# DataControlBoard-RPi.net
KiCad netlist of a schematic drawn in EAGLE
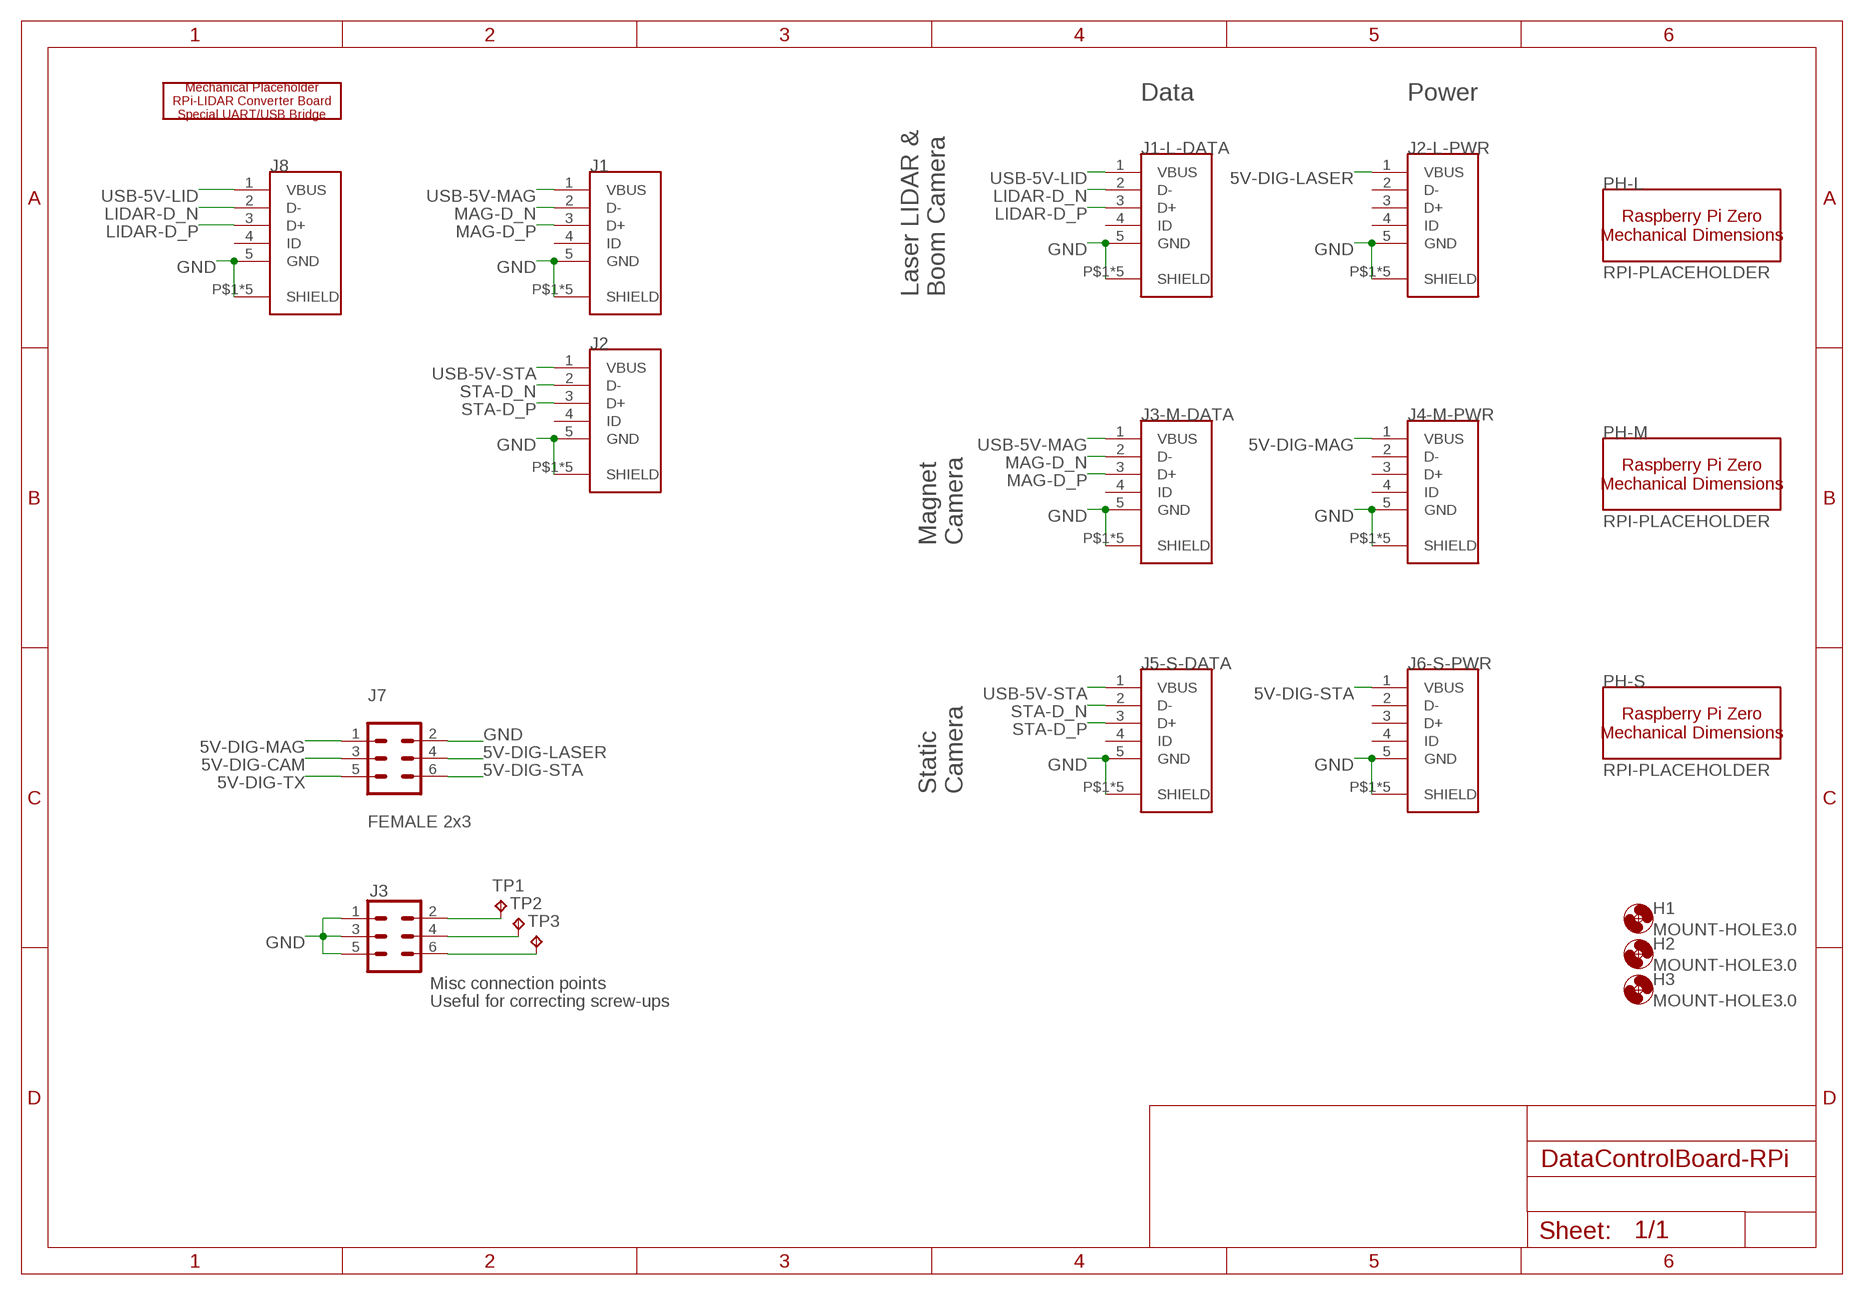
[diagram p0: schematic, sheet 1]

(export (version "E")
  (design (tool "Eeschema 10.0.6"))
  (components
    (comp (ref "H1")
      (value "MOUNT-HOLE3.0")
      (footprint "eagle-import:3,0")
      (libsource (lib "eagle-import") (part "MOUNT-HOLE3.0"))
    )
    (comp (ref "H2")
      (value "MOUNT-HOLE3.0")
      (footprint "eagle-import:3,0")
      (libsource (lib "eagle-import") (part "MOUNT-HOLE3.0"))
    )
    (comp (ref "H3")
      (value "MOUNT-HOLE3.0")
      (footprint "eagle-import:3,0")
      (libsource (lib "eagle-import") (part "MOUNT-HOLE3.0"))
    )
    (comp (ref "J1")
      (value "USB3150-30-130-AMANUFACTURABLE")
      (footprint "eagle-import:GCT_USB3150-30-EASIER")
      (libsource (lib "eagle-import") (part "USB3150-30-130-AMANUFACTURABLE"))
    )
    (comp (ref "J1-L-DATA")
      (value "USB3150-30-130-AMANUFACTURABLE")
      (footprint "eagle-import:GCT_USB3150-30-EASIER")
      (libsource (lib "eagle-import") (part "USB3150-30-130-AMANUFACTURABLE"))
    )
    (comp (ref "J2")
      (value "USB3150-30-130-AMANUFACTURABLE")
      (footprint "eagle-import:GCT_USB3150-30-EASIER")
      (libsource (lib "eagle-import") (part "USB3150-30-130-AMANUFACTURABLE"))
    )
    (comp (ref "J2-L-PWR")
      (value "USB3150-30-130-AMANUFACTURABLE")
      (footprint "eagle-import:GCT_USB3150-30-EASIER")
      (libsource (lib "eagle-import") (part "USB3150-30-130-AMANUFACTURABLE"))
    )
    (comp (ref "J3")
      (value "CONN_03X22X3_SILK_MALE_PTH")
      (footprint "eagle-import:2X3")
      (libsource (lib "eagle-import") (part "CONN_03X22X3_SILK_MALE_PTH"))
    )
    (comp (ref "J3-M-DATA")
      (value "USB3150-30-130-AMANUFACTURABLE")
      (footprint "eagle-import:GCT_USB3150-30-EASIER")
      (libsource (lib "eagle-import") (part "USB3150-30-130-AMANUFACTURABLE"))
    )
    (comp (ref "J4-M-PWR")
      (value "USB3150-30-130-AMANUFACTURABLE")
      (footprint "eagle-import:GCT_USB3150-30-EASIER")
      (libsource (lib "eagle-import") (part "USB3150-30-130-AMANUFACTURABLE"))
    )
    (comp (ref "J5-S-DATA")
      (value "USB3150-30-130-AMANUFACTURABLE")
      (footprint "eagle-import:GCT_USB3150-30-EASIER")
      (libsource (lib "eagle-import") (part "USB3150-30-130-AMANUFACTURABLE"))
    )
    (comp (ref "J6-S-PWR")
      (value "USB3150-30-130-AMANUFACTURABLE")
      (footprint "eagle-import:GCT_USB3150-30-EASIER")
      (libsource (lib "eagle-import") (part "USB3150-30-130-AMANUFACTURABLE"))
    )
    (comp (ref "J7")
      (value "FEMALE 2x3")
      (footprint "eagle-import:2X3")
      (libsource (lib "eagle-import") (part "CONN_03X2FEMALE"))
    )
    (comp (ref "J8")
      (value "USB3150-30-130-AMANUFACTURABLE")
      (footprint "eagle-import:GCT_USB3150-30-EASIER")
      (libsource (lib "eagle-import") (part "USB3150-30-130-AMANUFACTURABLE"))
    )
    (comp (ref "PH-L")
      (value "RPI-PLACEHOLDER")
      (footprint "eagle-import:RPI-ZERO-EDGE")
      (libsource (lib "eagle-import") (part "RPI-PLACEHOLDER"))
    )
    (comp (ref "PH-M")
      (value "RPI-PLACEHOLDER")
      (footprint "eagle-import:RPI-ZERO-EDGE")
      (libsource (lib "eagle-import") (part "RPI-PLACEHOLDER"))
    )
    (comp (ref "PH-S")
      (value "RPI-PLACEHOLDER")
      (footprint "eagle-import:RPI-ZERO-EDGE")
      (libsource (lib "eagle-import") (part "RPI-PLACEHOLDER"))
    )
    (comp (ref "TP1")
      (value "TPPAD1-17")
      (footprint "eagle-import:P1-17")
      (libsource (lib "eagle-import") (part "TPPAD1-17"))
    )
    (comp (ref "TP2")
      (value "TPPAD1-17")
      (footprint "eagle-import:P1-17")
      (libsource (lib "eagle-import") (part "TPPAD1-17"))
    )
    (comp (ref "TP3")
      (value "TPPAD1-17")
      (footprint "eagle-import:P1-17")
      (libsource (lib "eagle-import") (part "TPPAD1-17"))
    )
    (comp (ref "U$4")
      (value "LIDAR-CONV-PLACEHOLDER")
      (footprint "eagle-import:LIDAR-PLACEHOLDER")
      (libsource (lib "eagle-import") (part "LIDAR-CONV-PLACEHOLDER"))
    )
  )
  (nets
    (net (code "1") (name "/5V-DIG-CAM") (class "Default")
      (node (ref "J7") (pin "3") (pinfunction "3_3") (pintype "bidirectional"))
    )
    (net (code "2") (name "/5V-DIG-LASER") (class "Default")
      (node (ref "J2-L-PWR") (pin "1") (pinfunction "VBUS_1") (pintype "passive"))
      (node (ref "J7") (pin "4") (pinfunction "4_4") (pintype "bidirectional"))
    )
    (net (code "3") (name "/5V-DIG-MAG") (class "Default")
      (node (ref "J4-M-PWR") (pin "1") (pinfunction "VBUS_1") (pintype "passive"))
      (node (ref "J7") (pin "1") (pinfunction "1_1") (pintype "bidirectional"))
    )
    (net (code "4") (name "/5V-DIG-STA") (class "Default")
      (node (ref "J6-S-PWR") (pin "1") (pinfunction "VBUS_1") (pintype "passive"))
      (node (ref "J7") (pin "6") (pinfunction "6_6") (pintype "bidirectional"))
    )
    (net (code "5") (name "/5V-DIG-TX") (class "Default")
      (node (ref "J7") (pin "5") (pinfunction "5_5") (pintype "bidirectional"))
    )
    (net (code "6") (name "/GND") (class "Default")
      (node (ref "J1") (pin "5") (pinfunction "GND_5") (pintype "passive"))
      (node (ref "J1") (pin "P$1") (pinfunction "SHIELD_P$1") (pintype "passive"))
      (node (ref "J1") (pin "S3") (pinfunction "SHIELD_S3") (pintype "passive"))
      (node (ref "J1") (pin "S4") (pinfunction "SHIELD_S4") (pintype "passive"))
      (node (ref "J1") (pin "S5") (pinfunction "SHIELD_S5") (pintype "passive"))
      (node (ref "J1") (pin "S6") (pinfunction "SHIELD_S6") (pintype "passive"))
      (node (ref "J1-L-DATA") (pin "5") (pinfunction "GND_5") (pintype "passive"))
      (node (ref "J1-L-DATA") (pin "P$1") (pinfunction "SHIELD_P$1") (pintype "passive"))
      (node (ref "J1-L-DATA") (pin "S3") (pinfunction "SHIELD_S3") (pintype "passive"))
      (node (ref "J1-L-DATA") (pin "S4") (pinfunction "SHIELD_S4") (pintype "passive"))
      (node (ref "J1-L-DATA") (pin "S5") (pinfunction "SHIELD_S5") (pintype "passive"))
      (node (ref "J1-L-DATA") (pin "S6") (pinfunction "SHIELD_S6") (pintype "passive"))
      (node (ref "J2") (pin "5") (pinfunction "GND_5") (pintype "passive"))
      (node (ref "J2") (pin "P$1") (pinfunction "SHIELD_P$1") (pintype "passive"))
      (node (ref "J2") (pin "S3") (pinfunction "SHIELD_S3") (pintype "passive"))
      (node (ref "J2") (pin "S4") (pinfunction "SHIELD_S4") (pintype "passive"))
      (node (ref "J2") (pin "S5") (pinfunction "SHIELD_S5") (pintype "passive"))
      (node (ref "J2") (pin "S6") (pinfunction "SHIELD_S6") (pintype "passive"))
      (node (ref "J2-L-PWR") (pin "5") (pinfunction "GND_5") (pintype "passive"))
      (node (ref "J2-L-PWR") (pin "P$1") (pinfunction "SHIELD_P$1") (pintype "passive"))
      (node (ref "J2-L-PWR") (pin "S3") (pinfunction "SHIELD_S3") (pintype "passive"))
      (node (ref "J2-L-PWR") (pin "S4") (pinfunction "SHIELD_S4") (pintype "passive"))
      (node (ref "J2-L-PWR") (pin "S5") (pinfunction "SHIELD_S5") (pintype "passive"))
      (node (ref "J2-L-PWR") (pin "S6") (pinfunction "SHIELD_S6") (pintype "passive"))
      (node (ref "J3") (pin "1") (pinfunction "1_1") (pintype "bidirectional"))
      (node (ref "J3") (pin "3") (pinfunction "3_3") (pintype "bidirectional"))
      (node (ref "J3") (pin "5") (pinfunction "5_5") (pintype "bidirectional"))
      (node (ref "J3-M-DATA") (pin "5") (pinfunction "GND_5") (pintype "passive"))
      (node (ref "J3-M-DATA") (pin "P$1") (pinfunction "SHIELD_P$1") (pintype "passive"))
      (node (ref "J3-M-DATA") (pin "S3") (pinfunction "SHIELD_S3") (pintype "passive"))
      (node (ref "J3-M-DATA") (pin "S4") (pinfunction "SHIELD_S4") (pintype "passive"))
      (node (ref "J3-M-DATA") (pin "S5") (pinfunction "SHIELD_S5") (pintype "passive"))
      (node (ref "J3-M-DATA") (pin "S6") (pinfunction "SHIELD_S6") (pintype "passive"))
      (node (ref "J4-M-PWR") (pin "5") (pinfunction "GND_5") (pintype "passive"))
      (node (ref "J4-M-PWR") (pin "P$1") (pinfunction "SHIELD_P$1") (pintype "passive"))
      (node (ref "J4-M-PWR") (pin "S3") (pinfunction "SHIELD_S3") (pintype "passive"))
      (node (ref "J4-M-PWR") (pin "S4") (pinfunction "SHIELD_S4") (pintype "passive"))
      (node (ref "J4-M-PWR") (pin "S5") (pinfunction "SHIELD_S5") (pintype "passive"))
      (node (ref "J4-M-PWR") (pin "S6") (pinfunction "SHIELD_S6") (pintype "passive"))
      (node (ref "J5-S-DATA") (pin "5") (pinfunction "GND_5") (pintype "passive"))
      (node (ref "J5-S-DATA") (pin "P$1") (pinfunction "SHIELD_P$1") (pintype "passive"))
      (node (ref "J5-S-DATA") (pin "S3") (pinfunction "SHIELD_S3") (pintype "passive"))
      (node (ref "J5-S-DATA") (pin "S4") (pinfunction "SHIELD_S4") (pintype "passive"))
      (node (ref "J5-S-DATA") (pin "S5") (pinfunction "SHIELD_S5") (pintype "passive"))
      (node (ref "J5-S-DATA") (pin "S6") (pinfunction "SHIELD_S6") (pintype "passive"))
      (node (ref "J6-S-PWR") (pin "5") (pinfunction "GND_5") (pintype "passive"))
      (node (ref "J6-S-PWR") (pin "P$1") (pinfunction "SHIELD_P$1") (pintype "passive"))
      (node (ref "J6-S-PWR") (pin "S3") (pinfunction "SHIELD_S3") (pintype "passive"))
      (node (ref "J6-S-PWR") (pin "S4") (pinfunction "SHIELD_S4") (pintype "passive"))
      (node (ref "J6-S-PWR") (pin "S5") (pinfunction "SHIELD_S5") (pintype "passive"))
      (node (ref "J6-S-PWR") (pin "S6") (pinfunction "SHIELD_S6") (pintype "passive"))
      (node (ref "J7") (pin "2") (pinfunction "2_2") (pintype "bidirectional"))
      (node (ref "J8") (pin "5") (pinfunction "GND_5") (pintype "passive"))
      (node (ref "J8") (pin "P$1") (pinfunction "SHIELD_P$1") (pintype "passive"))
      (node (ref "J8") (pin "S3") (pinfunction "SHIELD_S3") (pintype "passive"))
      (node (ref "J8") (pin "S4") (pinfunction "SHIELD_S4") (pintype "passive"))
      (node (ref "J8") (pin "S5") (pinfunction "SHIELD_S5") (pintype "passive"))
      (node (ref "J8") (pin "S6") (pinfunction "SHIELD_S6") (pintype "passive"))
    )
    (net (code "7") (name "/LIDAR-D_N") (class "Default")
      (node (ref "J1-L-DATA") (pin "2") (pinfunction "D-_2") (pintype "passive"))
      (node (ref "J8") (pin "2") (pinfunction "D-_2") (pintype "passive"))
    )
    (net (code "8") (name "/LIDAR-D_P") (class "Default")
      (node (ref "J1-L-DATA") (pin "3") (pinfunction "D+_3") (pintype "passive"))
      (node (ref "J8") (pin "3") (pinfunction "D+_3") (pintype "passive"))
    )
    (net (code "9") (name "/MAG-D_N") (class "Default")
      (node (ref "J1") (pin "2") (pinfunction "D-_2") (pintype "passive"))
      (node (ref "J3-M-DATA") (pin "2") (pinfunction "D-_2") (pintype "passive"))
    )
    (net (code "10") (name "/MAG-D_P") (class "Default")
      (node (ref "J1") (pin "3") (pinfunction "D+_3") (pintype "passive"))
      (node (ref "J3-M-DATA") (pin "3") (pinfunction "D+_3") (pintype "passive"))
    )
    (net (code "11") (name "/STA-D_N") (class "Default")
      (node (ref "J2") (pin "2") (pinfunction "D-_2") (pintype "passive"))
      (node (ref "J5-S-DATA") (pin "2") (pinfunction "D-_2") (pintype "passive"))
    )
    (net (code "12") (name "/STA-D_P") (class "Default")
      (node (ref "J2") (pin "3") (pinfunction "D+_3") (pintype "passive"))
      (node (ref "J5-S-DATA") (pin "3") (pinfunction "D+_3") (pintype "passive"))
    )
    (net (code "13") (name "/USB-5V-LID") (class "Default")
      (node (ref "J1-L-DATA") (pin "1") (pinfunction "VBUS_1") (pintype "passive"))
      (node (ref "J8") (pin "1") (pinfunction "VBUS_1") (pintype "passive"))
    )
    (net (code "14") (name "/USB-5V-MAG") (class "Default")
      (node (ref "J1") (pin "1") (pinfunction "VBUS_1") (pintype "passive"))
      (node (ref "J3-M-DATA") (pin "1") (pinfunction "VBUS_1") (pintype "passive"))
    )
    (net (code "15") (name "/USB-5V-STA") (class "Default")
      (node (ref "J2") (pin "1") (pinfunction "VBUS_1") (pintype "passive"))
      (node (ref "J5-S-DATA") (pin "1") (pinfunction "VBUS_1") (pintype "passive"))
    )
    (net (code "16") (name "Net-(J3-Pad2)") (class "Default")
      (node (ref "J3") (pin "2") (pinfunction "2_2") (pintype "bidirectional"))
      (node (ref "TP1") (pin "TP") (pinfunction "TP_TP") (pintype "input"))
    )
    (net (code "17") (name "Net-(J3-Pad4)") (class "Default")
      (node (ref "J3") (pin "4") (pinfunction "4_4") (pintype "bidirectional"))
      (node (ref "TP2") (pin "TP") (pinfunction "TP_TP") (pintype "input"))
    )
    (net (code "18") (name "Net-(J3-Pad6)") (class "Default")
      (node (ref "J3") (pin "6") (pinfunction "6_6") (pintype "bidirectional"))
      (node (ref "TP3") (pin "TP") (pinfunction "TP_TP") (pintype "input"))
    )
    (net (code "19") (name "unconnected-(J1-ID-Pad4)") (class "Default")
      (node (ref "J1") (pin "4") (pinfunction "ID_4") (pintype "passive"))
    )
    (net (code "20") (name "unconnected-(J1-L-DATA-ID-Pad4)") (class "Default")
      (node (ref "J1-L-DATA") (pin "4") (pinfunction "ID_4") (pintype "passive"))
    )
    (net (code "21") (name "unconnected-(J2-ID-Pad4)") (class "Default")
      (node (ref "J2") (pin "4") (pinfunction "ID_4") (pintype "passive"))
    )
    (net (code "22") (name "unconnected-(J2-L-PWR-D+-Pad3)") (class "Default")
      (node (ref "J2-L-PWR") (pin "3") (pinfunction "D+_3") (pintype "passive"))
    )
    (net (code "23") (name "unconnected-(J2-L-PWR-D--Pad2)") (class "Default")
      (node (ref "J2-L-PWR") (pin "2") (pinfunction "D-_2") (pintype "passive"))
    )
    (net (code "24") (name "unconnected-(J2-L-PWR-ID-Pad4)") (class "Default")
      (node (ref "J2-L-PWR") (pin "4") (pinfunction "ID_4") (pintype "passive"))
    )
    (net (code "25") (name "unconnected-(J3-M-DATA-ID-Pad4)") (class "Default")
      (node (ref "J3-M-DATA") (pin "4") (pinfunction "ID_4") (pintype "passive"))
    )
    (net (code "26") (name "unconnected-(J4-M-PWR-D+-Pad3)") (class "Default")
      (node (ref "J4-M-PWR") (pin "3") (pinfunction "D+_3") (pintype "passive"))
    )
    (net (code "27") (name "unconnected-(J4-M-PWR-D--Pad2)") (class "Default")
      (node (ref "J4-M-PWR") (pin "2") (pinfunction "D-_2") (pintype "passive"))
    )
    (net (code "28") (name "unconnected-(J4-M-PWR-ID-Pad4)") (class "Default")
      (node (ref "J4-M-PWR") (pin "4") (pinfunction "ID_4") (pintype "passive"))
    )
    (net (code "29") (name "unconnected-(J5-S-DATA-ID-Pad4)") (class "Default")
      (node (ref "J5-S-DATA") (pin "4") (pinfunction "ID_4") (pintype "passive"))
    )
    (net (code "30") (name "unconnected-(J6-S-PWR-D+-Pad3)") (class "Default")
      (node (ref "J6-S-PWR") (pin "3") (pinfunction "D+_3") (pintype "passive"))
    )
    (net (code "31") (name "unconnected-(J6-S-PWR-D--Pad2)") (class "Default")
      (node (ref "J6-S-PWR") (pin "2") (pinfunction "D-_2") (pintype "passive"))
    )
    (net (code "32") (name "unconnected-(J6-S-PWR-ID-Pad4)") (class "Default")
      (node (ref "J6-S-PWR") (pin "4") (pinfunction "ID_4") (pintype "passive"))
    )
    (net (code "33") (name "unconnected-(J8-ID-Pad4)") (class "Default")
      (node (ref "J8") (pin "4") (pinfunction "ID_4") (pintype "passive"))
    )
  )
)
